# ESP32_Watch_Project_V2_0.net
KiCad netlist of a schematic drawn in Altium Designer
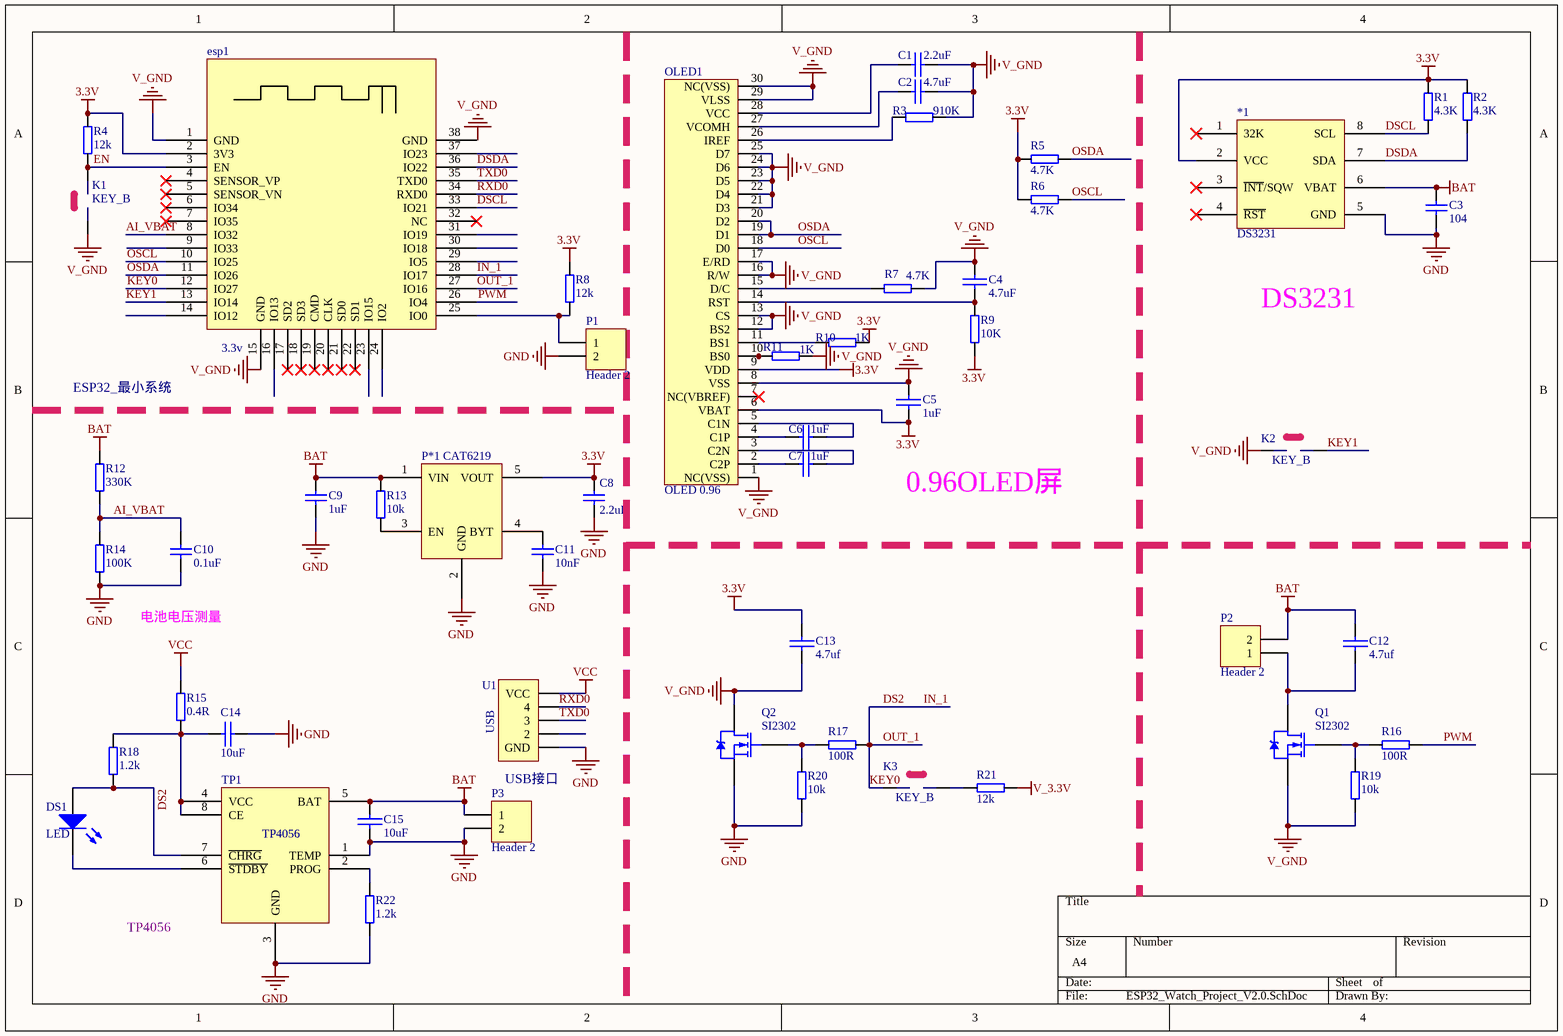
[diagram p0: ESP32_Watch_Project_V2.0.SchDoc]

(export (version "E")
  (design (tool "Eeschema 10.0.6"))
  (components
    (comp (ref "*1")
      (value "DS3231")
      (footprint "2104")
      (libsource (lib "ESP32_DOWN_Project") (part "DS3231"))
    )
    (comp (ref "C1")
      (value "2.2uF")
      (footprint "ESP32_DOWN_1_6:R0603")
      (description "Capacitor")
      (libsource (lib "ZigBee应用模块V2.1") (part "CAP"))
    )
    (comp (ref "C2")
      (value "4.7uF")
      (footprint "R0603")
      (description "Capacitor")
      (libsource (lib "ZigBee应用模块V2.1") (part "CAP"))
    )
    (comp (ref "C3")
      (value "104")
      (footprint "R0603")
      (description "Capacitor")
      (fields (field (name "PUBLISHER") "Altium Limited"))
      (libsource (lib "蓝牙可穿戴") (part "Cap_1"))
    )
    (comp (ref "C4")
      (value "4.7uF")
      (footprint "R0603")
      (description "Capacitor")
      (libsource (lib "ZigBee应用模块V2.1") (part "CAP"))
    )
    (comp (ref "C5")
      (value "1uF")
      (footprint "R0603")
      (description "Capacitor")
      (libsource (lib "ZigBee应用模块V2.1") (part "CAP"))
    )
    (comp (ref "C6")
      (value "1uF")
      (footprint "ESP32_DOWN_1_6:R0603")
      (description "Capacitor")
      (libsource (lib "ZigBee应用模块V2.1") (part "CAP"))
    )
    (comp (ref "C7")
      (value "1uF")
      (footprint "ESP32_DOWN_1_6:R0603")
      (description "Capacitor")
      (libsource (lib "ZigBee应用模块V2.1") (part "CAP"))
    )
    (comp (ref "C8")
      (value "2.2uF")
      (footprint "R0603")
      (description "Capacitor")
      (fields (field (name "PUBLISHER") "Altium Limited"))
      (libsource (lib "CC26XX转接板") (part "Cap_1"))
    )
    (comp (ref "C9")
      (value "1uF")
      (footprint "R0603")
      (description "Capacitor")
      (fields (field (name "PUBLISHER") "Altium Limited"))
      (libsource (lib "CC26XX转接板") (part "Cap_1"))
    )
    (comp (ref "C10")
      (value "0.1uF")
      (footprint "R0603")
      (description "Capacitor")
      (fields (field (name "PUBLISHER") "Altium Limited"))
      (libsource (lib "CC26XX转接板") (part "Cap_1"))
    )
    (comp (ref "C11")
      (value "10nF")
      (footprint "R0603")
      (description "Capacitor")
      (fields (field (name "PUBLISHER") "Altium Limited"))
      (libsource (lib "CC26XX转接板") (part "Cap_1"))
    )
    (comp (ref "C12")
      (value "4.7uf")
      (footprint "ESP32_DOWN_1_6:R0603")
      (description "Capacitor")
      (libsource (lib "ZigBee应用模块V2.1") (part "CAP"))
    )
    (comp (ref "C13")
      (value "4.7uf")
      (footprint "ESP32_DOWN_1_6:R0603")
      (description "Capacitor")
      (libsource (lib "ZigBee应用模块V2.1") (part "CAP"))
    )
    (comp (ref "C14")
      (value "10uF")
      (footprint "R0603")
      (description "Capacitor")
      (libsource (lib "ZigBee应用模块V2.1") (part "CAP"))
    )
    (comp (ref "C15")
      (value "10uF")
      (footprint "R0603")
      (description "Capacitor")
      (libsource (lib "ZigBee应用模块V2.1") (part "CAP"))
    )
    (comp (ref "DS1")
      (value "LED")
      (footprint "SMDLED")
      (description "Typical RED, GREEN, YELLOW, AMBER GaAs LED")
      (fields (field (name "PUBLISHER") "Altium Limited"))
      (libsource (lib "战舰STM32开发板底板封装库") (part "LED2"))
    )
    (comp (ref "esp1")
      (value "3.3v")
      (footprint "esp32_cord")
      (libsource (lib "ESP32_DOWN_Project") (part "esp32_core"))
    )
    (comp (ref "K1") (value "KEY_B") (footprint "KEY_b") (libsource (lib "ESP32_UP_Project") (part "KEY_B")))
    (comp (ref "K2")
      (value "KEY_B")
      (footprint "ESP32_DOWN_1_6:KEY_b")
      (libsource (lib "蓝牙可穿戴") (part "KEY_B"))
    )
    (comp (ref "K3")
      (value "KEY_B")
      (footprint "ESP32_DOWN_1_6:KEY_b")
      (libsource (lib "蓝牙可穿戴") (part "KEY_B"))
    )
    (comp (ref "OLED1") (value "OLED 0.96") (footprint "0.96_OLED") (libsource (lib "蓝牙可穿戴") (part "OLED")))
    (comp (ref "P*1")
      (value "CAT6219")
      (footprint "CAT6219")
      (libsource (lib "ESP32_DOWN_Project") (part "CAT6219"))
    )
    (comp (ref "P1")
      (value "Header 2")
      (footprint "HDR1X2")
      (description "Header, 2-Pin")
      (fields (field (name "PUBLISHER") "Altium Limited"))
      (libsource (lib "") (part "Header 2_1"))
    )
    (comp (ref "P2")
      (value "Header 2")
      (footprint "HDR1X2")
      (description "Header, 2-Pin")
      (fields (field (name "PUBLISHER") "Altium Limited"))
      (libsource (lib "Miscellaneous Connectors") (part "Header 2"))
    )
    (comp (ref "P3")
      (value "Header 2")
      (footprint "HDR1X2")
      (description "Header, 2-Pin")
      (fields (field (name "PUBLISHER") "Altium Limited"))
      (libsource (lib "") (part "Header 2_1"))
    )
    (comp (ref "Q1")
      (value "SI2302")
      (footprint "SOT-23(SOT-23-3)")
      (description "N-Channel Power MOSFET")
      (fields (field (name "PUBLISHER") "mazhongwei"))
      (libsource (lib "RoboFly") (part "SI2302"))
    )
    (comp (ref "Q2")
      (value "SI2302")
      (footprint "SOT-23(SOT-23-3)")
      (description "N-Channel Power MOSFET")
      (fields (field (name "PUBLISHER") "mazhongwei"))
      (libsource (lib "RoboFly") (part "SI2302"))
    )
    (comp (ref "R1") (value "4.3K") (footprint "C0603") (libsource (lib "蓝牙可穿戴") (part "Res")))
    (comp (ref "R2") (value "4.3K") (footprint "C0603") (libsource (lib "蓝牙可穿戴") (part "Res")))
    (comp (ref "R3") (value "910K") (footprint "C0603") (libsource (lib "蓝牙可穿戴") (part "Res")))
    (comp (ref "R4") (value "12k") (footprint "C0603") (libsource (lib "蓝牙可穿戴") (part "Res")))
    (comp (ref "R5") (value "4.7K") (footprint "C0603") (libsource (lib "蓝牙可穿戴") (part "Res")))
    (comp (ref "R6") (value "4.7K") (footprint "C0603") (libsource (lib "蓝牙可穿戴") (part "Res")))
    (comp (ref "R7") (value "4.7K") (footprint "C0603") (libsource (lib "蓝牙可穿戴") (part "Res")))
    (comp (ref "R8") (value "12k") (footprint "C0603") (libsource (lib "蓝牙可穿戴") (part "Res")))
    (comp (ref "R9") (value "10K") (footprint "C0603") (libsource (lib "蓝牙可穿戴") (part "Res")))
    (comp (ref "R10") (value "1K") (footprint "C0603") (libsource (lib "蓝牙可穿戴") (part "Res")))
    (comp (ref "R11") (value "1K") (footprint "C0603") (libsource (lib "蓝牙可穿戴") (part "Res")))
    (comp (ref "R12") (value "330K") (footprint "C0603") (libsource (lib "蓝牙可穿戴") (part "Res")))
    (comp (ref "R13") (value "10k") (footprint "C0603") (libsource (lib "蓝牙可穿戴") (part "Res")))
    (comp (ref "R14") (value "100K") (footprint "C0603") (libsource (lib "蓝牙可穿戴") (part "Res")))
    (comp (ref "R15") (value "0.4R") (footprint "C0603") (libsource (lib "蓝牙可穿戴") (part "Res")))
    (comp (ref "R16") (value "100R") (footprint "C0603") (libsource (lib "蓝牙可穿戴") (part "Res")))
    (comp (ref "R17") (value "100R") (footprint "C0603") (libsource (lib "蓝牙可穿戴") (part "Res")))
    (comp (ref "R18") (value "1.2k") (footprint "C0603") (libsource (lib "蓝牙可穿戴") (part "Res")))
    (comp (ref "R19") (value "10k") (footprint "C0603") (libsource (lib "蓝牙可穿戴") (part "Res")))
    (comp (ref "R20") (value "10k") (footprint "C0603") (libsource (lib "蓝牙可穿戴") (part "Res")))
    (comp (ref "R21") (value "12k") (footprint "C0603") (libsource (lib "蓝牙可穿戴") (part "Res")))
    (comp (ref "R22") (value "1.2k") (footprint "C0603") (libsource (lib "蓝牙可穿戴") (part "Res")))
    (comp (ref "TP1") (value "TP4056") (footprint "2104") (libsource (lib "TP4056") (part "TP4056")))
    (comp (ref "U1") (value "U?") (footprint "type_a") (libsource (lib "ESP32_DOWN_Project") (part "type_a")))
  )
  (nets
    (net (code "1") (name "/AI_VBAT") (class "Default")
      (node (ref "C10") (pin "2") (pinfunction "2_2") (pintype "passive"))
      (node (ref "R12") (pin "1") (pintype "passive"))
      (node (ref "R14") (pin "2") (pintype "passive"))
      (node (ref "esp1") (pin "8") (pinfunction "IO32_8") (pintype "passive"))
    )
    (net (code "2") (name "/DS2") (class "Default")
      (node (ref "DS1") (pin "1") (pinfunction "A_1") (pintype "passive"))
      (node (ref "R17") (pin "1") (pintype "passive"))
      (node (ref "R18") (pin "2") (pintype "passive"))
      (node (ref "TP1") (pin "7") (pinfunction "~{CHRG}_7") (pintype "passive"))
      (node (ref "esp1") (pin "27") (pinfunction "IO16_27") (pintype "passive"))
      (node (ref "esp1") (pin "28") (pinfunction "IO17_28") (pintype "passive"))
    )
    (net (code "3") (name "/DSCL") (class "Default")
      (node (ref "*1") (pin "8") (pinfunction "SCL_8") (pintype "passive"))
      (node (ref "R1") (pin "2") (pintype "passive"))
      (node (ref "esp1") (pin "33") (pinfunction "IO21_33") (pintype "passive"))
    )
    (net (code "4") (name "/DSDA") (class "Default")
      (node (ref "*1") (pin "7") (pinfunction "SDA_7") (pintype "passive"))
      (node (ref "R2") (pin "2") (pintype "passive"))
      (node (ref "esp1") (pin "36") (pinfunction "IO22_36") (pintype "passive"))
    )
    (net (code "5") (name "/EN") (class "Default")
      (node (ref "K1") (pin "2") (pinfunction "2_2") (pintype "passive"))
      (node (ref "R4") (pin "1") (pintype "passive"))
      (node (ref "esp1") (pin "3") (pinfunction "EN_3") (pintype "passive"))
    )
    (net (code "6") (name "/KEY0") (class "Default")
      (node (ref "K3") (pin "1") (pinfunction "1_1") (pintype "passive"))
      (node (ref "esp1") (pin "12") (pinfunction "IO27_12") (pintype "passive"))
    )
    (net (code "7") (name "/KEY1") (class "Default")
      (node (ref "K2") (pin "2") (pinfunction "2_2") (pintype "passive"))
      (node (ref "esp1") (pin "13") (pinfunction "IO14_13") (pintype "passive"))
    )
    (net (code "8") (name "/OSCL") (class "Default")
      (node (ref "OLED1") (pin "18") (pinfunction "D0_18") (pintype "passive"))
      (node (ref "R6") (pin "1") (pintype "passive"))
      (node (ref "esp1") (pin "10") (pinfunction "IO25_10") (pintype "passive"))
    )
    (net (code "9") (name "/OSDA") (class "Default")
      (node (ref "OLED1") (pin "19") (pinfunction "D1_19") (pintype "passive"))
      (node (ref "OLED1") (pin "20") (pinfunction "D2_20") (pintype "passive"))
      (node (ref "R5") (pin "1") (pintype "passive"))
      (node (ref "esp1") (pin "11") (pinfunction "IO26_11") (pintype "passive"))
    )
    (net (code "10") (name "/PWM") (class "Default")
      (node (ref "R16") (pin "1") (pintype "passive"))
      (node (ref "esp1") (pin "26") (pinfunction "IO4_26") (pintype "passive"))
    )
    (net (code "11") (name "/RXD0") (class "Default")
      (node (ref "U1") (pin "4") (pinfunction "4_4") (pintype "passive"))
      (node (ref "esp1") (pin "34") (pinfunction "RXD0_34") (pintype "passive"))
    )
    (net (code "12") (name "/TXD0") (class "Default")
      (node (ref "U1") (pin "3") (pinfunction "3_3") (pintype "passive"))
      (node (ref "esp1") (pin "35") (pinfunction "TXD0_35") (pintype "passive"))
    )
    (net (code "13") (name "3.3V") (class "Default")
      (node (ref "*1") (pin "2") (pinfunction "VCC_2") (pintype "passive"))
      (node (ref "C13") (pin "1") (pinfunction "1_1") (pintype "passive"))
      (node (ref "C5") (pin "1") (pinfunction "1_1") (pintype "passive"))
      (node (ref "C8") (pin "2") (pinfunction "2_2") (pintype "passive"))
      (node (ref "OLED1") (pin "6") (pinfunction "VBAT_6") (pintype "passive"))
      (node (ref "OLED1") (pin "9") (pinfunction "VDD_9") (pintype "passive"))
      (node (ref "P*1") (pin "5") (pinfunction "VOUT_5") (pintype "passive"))
      (node (ref "R1") (pin "1") (pintype "passive"))
      (node (ref "R10") (pin "1") (pintype "passive"))
      (node (ref "R2") (pin "1") (pintype "passive"))
      (node (ref "R4") (pin "2") (pintype "passive"))
      (node (ref "R5") (pin "2") (pintype "passive"))
      (node (ref "R6") (pin "2") (pintype "passive"))
      (node (ref "R8") (pin "2") (pintype "passive"))
      (node (ref "R9") (pin "2") (pintype "passive"))
      (node (ref "esp1") (pin "2") (pinfunction "3V3_2") (pintype "passive"))
    )
    (net (code "14") (name "BAT") (class "Default")
      (node (ref "*1") (pin "6") (pinfunction "VBAT_6") (pintype "passive"))
      (node (ref "C12") (pin "1") (pinfunction "1_1") (pintype "passive"))
      (node (ref "C15") (pin "2") (pinfunction "2_2") (pintype "passive"))
      (node (ref "C3") (pin "2") (pinfunction "2_2") (pintype "passive"))
      (node (ref "C9") (pin "2") (pinfunction "2_2") (pintype "passive"))
      (node (ref "P*1") (pin "1") (pinfunction "VIN_1") (pintype "passive"))
      (node (ref "P2") (pin "2") (pinfunction "2_2") (pintype "passive"))
      (node (ref "P3") (pin "1") (pinfunction "1_1") (pintype "passive"))
      (node (ref "R12") (pin "2") (pintype "passive"))
      (node (ref "R13") (pin "2") (pintype "passive"))
      (node (ref "TP1") (pin "5") (pinfunction "BAT_5") (pintype "passive"))
    )
    (net (code "15") (name "GND") (class "Default")
      (node (ref "*1") (pin "5") (pinfunction "GND_5") (pintype "passive"))
      (node (ref "C10") (pin "1") (pinfunction "1_1") (pintype "passive"))
      (node (ref "C11") (pin "1") (pinfunction "1_1") (pintype "passive"))
      (node (ref "C14") (pin "2") (pinfunction "2_2") (pintype "passive"))
      (node (ref "C15") (pin "1") (pinfunction "1_1") (pintype "passive"))
      (node (ref "C3") (pin "1") (pinfunction "1_1") (pintype "passive"))
      (node (ref "C8") (pin "1") (pinfunction "1_1") (pintype "passive"))
      (node (ref "C9") (pin "1") (pinfunction "1_1") (pintype "passive"))
      (node (ref "P*1") (pin "2") (pinfunction "GND_2") (pintype "passive"))
      (node (ref "P1") (pin "2") (pinfunction "2_2") (pintype "passive"))
      (node (ref "P3") (pin "2") (pinfunction "2_2") (pintype "passive"))
      (node (ref "Q2") (pin "2") (pinfunction "S_2") (pintype "passive"))
      (node (ref "R14") (pin "1") (pintype "passive"))
      (node (ref "R20") (pin "1") (pintype "passive"))
      (node (ref "R22") (pin "2") (pintype "passive"))
      (node (ref "TP1") (pin "1") (pinfunction "TEMP_1") (pintype "passive"))
      (node (ref "TP1") (pin "3") (pinfunction "GND_3") (pintype "passive"))
      (node (ref "U1") (pin "1") (pinfunction "GND_1") (pintype "passive"))
    )
    (net (code "16") (name "Net-(DS1-K)") (class "Default")
      (node (ref "DS1") (pin "2") (pinfunction "K_2") (pintype "passive"))
      (node (ref "TP1") (pin "6") (pinfunction "~{STDBY}_6") (pintype "passive"))
    )
    (net (code "17") (name "Net-(K3-Pad2)") (class "Default")
      (node (ref "K3") (pin "2") (pinfunction "2_2") (pintype "passive"))
      (node (ref "R21") (pin "2") (pintype "passive"))
    )
    (net (code "18") (name "Net-(OLED1-BS0)") (class "Default")
      (node (ref "OLED1") (pin "10") (pinfunction "BS0_10") (pintype "passive"))
      (node (ref "R11") (pin "2") (pintype "passive"))
    )
    (net (code "19") (name "Net-(OLED1-BS1)") (class "Default")
      (node (ref "OLED1") (pin "11") (pinfunction "BS1_11") (pintype "passive"))
      (node (ref "R10") (pin "2") (pintype "passive"))
    )
    (net (code "20") (name "Net-(OLED1-C1N)") (class "Default")
      (node (ref "C6") (pin "1") (pinfunction "1_1") (pintype "passive"))
      (node (ref "OLED1") (pin "5") (pinfunction "C1N_5") (pintype "passive"))
    )
    (net (code "21") (name "Net-(OLED1-C1P)") (class "Default")
      (node (ref "C6") (pin "2") (pinfunction "2_2") (pintype "passive"))
      (node (ref "OLED1") (pin "4") (pinfunction "C1P_4") (pintype "passive"))
    )
    (net (code "22") (name "Net-(OLED1-C2N)") (class "Default")
      (node (ref "C7") (pin "1") (pinfunction "1_1") (pintype "passive"))
      (node (ref "OLED1") (pin "3") (pinfunction "C2N_3") (pintype "passive"))
    )
    (net (code "23") (name "Net-(OLED1-C2P)") (class "Default")
      (node (ref "C7") (pin "2") (pinfunction "2_2") (pintype "passive"))
      (node (ref "OLED1") (pin "2") (pinfunction "C2P_2") (pintype "passive"))
    )
    (net (code "24") (name "Net-(OLED1-D3)") (class "Default")
      (node (ref "OLED1") (pin "21") (pinfunction "D3_21") (pintype "passive"))
      (node (ref "OLED1") (pin "22") (pinfunction "D4_22") (pintype "passive"))
      (node (ref "OLED1") (pin "23") (pinfunction "D5_23") (pintype "passive"))
      (node (ref "OLED1") (pin "24") (pinfunction "D6_24") (pintype "passive"))
      (node (ref "OLED1") (pin "25") (pinfunction "D7_25") (pintype "passive"))
    )
    (net (code "25") (name "Net-(OLED1-D{slash}C)") (class "Default")
      (node (ref "OLED1") (pin "15") (pinfunction "D/C_15") (pintype "passive"))
      (node (ref "R7") (pin "1") (pintype "passive"))
    )
    (net (code "26") (name "Net-(OLED1-IREF)") (class "Default")
      (node (ref "OLED1") (pin "26") (pinfunction "IREF_26") (pintype "passive"))
      (node (ref "R3") (pin "1") (pintype "passive"))
    )
    (net (code "27") (name "Net-(OLED1-RST)") (class "Default")
      (node (ref "C4") (pin "1") (pinfunction "1_1") (pintype "passive"))
      (node (ref "OLED1") (pin "14") (pinfunction "RST_14") (pintype "passive"))
      (node (ref "R9") (pin "1") (pintype "passive"))
    )
    (net (code "28") (name "Net-(OLED1-VCC)") (class "Default")
      (node (ref "C1") (pin "1") (pinfunction "1_1") (pintype "passive"))
      (node (ref "OLED1") (pin "28") (pinfunction "VCC_28") (pintype "passive"))
    )
    (net (code "29") (name "Net-(OLED1-VCOMH)") (class "Default")
      (node (ref "C2") (pin "1") (pinfunction "1_1") (pintype "passive"))
      (node (ref "OLED1") (pin "27") (pinfunction "VCOMH_27") (pintype "passive"))
    )
    (net (code "30") (name "Net-(P*1-BYT)") (class "Default")
      (node (ref "C11") (pin "2") (pinfunction "2_2") (pintype "passive"))
      (node (ref "P*1") (pin "4") (pinfunction "BYT_4") (pintype "passive"))
    )
    (net (code "31") (name "Net-(P*1-EN)") (class "Default")
      (node (ref "P*1") (pin "3") (pinfunction "EN_3") (pintype "passive"))
      (node (ref "R13") (pin "1") (pintype "passive"))
    )
    (net (code "32") (name "Net-(Q1-D)") (class "Default")
      (node (ref "C12") (pin "2") (pinfunction "2_2") (pintype "passive"))
      (node (ref "P2") (pin "1") (pinfunction "1_1") (pintype "passive"))
      (node (ref "Q1") (pin "3") (pinfunction "D_3") (pintype "passive"))
    )
    (net (code "33") (name "Net-(Q1-G)") (class "Default")
      (node (ref "Q1") (pin "1") (pinfunction "G_1") (pintype "passive"))
      (node (ref "R16") (pin "2") (pintype "passive"))
      (node (ref "R19") (pin "2") (pintype "passive"))
    )
    (net (code "34") (name "Net-(Q2-G)") (class "Default")
      (node (ref "Q2") (pin "1") (pinfunction "G_1") (pintype "passive"))
      (node (ref "R17") (pin "2") (pintype "passive"))
      (node (ref "R20") (pin "2") (pintype "passive"))
    )
    (net (code "35") (name "Net-(TP1-CE)") (class "Default")
      (node (ref "C14") (pin "1") (pinfunction "1_1") (pintype "passive"))
      (node (ref "R15") (pin "2") (pintype "passive"))
      (node (ref "R18") (pin "1") (pintype "passive"))
      (node (ref "TP1") (pin "4") (pinfunction "VCC_4") (pintype "passive"))
      (node (ref "TP1") (pin "8") (pinfunction "CE_8") (pintype "passive"))
    )
    (net (code "36") (name "Net-(TP1-PROG)") (class "Default")
      (node (ref "R22") (pin "1") (pintype "passive"))
      (node (ref "TP1") (pin "2") (pinfunction "PROG_2") (pintype "passive"))
    )
    (net (code "37") (name "Net-(esp1-IO0)") (class "Default")
      (node (ref "P1") (pin "1") (pinfunction "1_1") (pintype "passive"))
      (node (ref "R8") (pin "1") (pintype "passive"))
      (node (ref "esp1") (pin "25") (pinfunction "IO0_25") (pintype "passive"))
    )
    (net (code "38") (name "VCC") (class "Default")
      (node (ref "R15") (pin "1") (pintype "passive"))
      (node (ref "U1") (pin "5") (pinfunction "VCC_5") (pintype "passive"))
    )
    (net (code "39") (name "V_3.3V") (class "Default") (node (ref "R21") (pin "1") (pintype "passive")))
    (net (code "40") (name "V_GND") (class "Default")
      (node (ref "C1") (pin "2") (pinfunction "2_2") (pintype "passive"))
      (node (ref "C13") (pin "2") (pinfunction "2_2") (pintype "passive"))
      (node (ref "C2") (pin "2") (pinfunction "2_2") (pintype "passive"))
      (node (ref "C4") (pin "2") (pinfunction "2_2") (pintype "passive"))
      (node (ref "C5") (pin "2") (pinfunction "2_2") (pintype "passive"))
      (node (ref "K1") (pin "1") (pinfunction "1_1") (pintype "passive"))
      (node (ref "OLED1") (pin "1") (pinfunction "NC(VSS)_1") (pintype "passive"))
      (node (ref "OLED1") (pin "12") (pinfunction "BS2_12") (pintype "passive"))
      (node (ref "OLED1") (pin "13") (pinfunction "CS_13") (pintype "passive"))
      (node (ref "OLED1") (pin "16") (pinfunction "R/W_16") (pintype "passive"))
      (node (ref "OLED1") (pin "17") (pinfunction "E/RD_17") (pintype "passive"))
      (node (ref "OLED1") (pin "29") (pinfunction "VLSS_29") (pintype "passive"))
      (node (ref "OLED1") (pin "30") (pinfunction "NC(VSS)_30") (pintype "passive"))
      (node (ref "OLED1") (pin "8") (pinfunction "VSS_8") (pintype "passive"))
      (node (ref "Q1") (pin "2") (pinfunction "S_2") (pintype "passive"))
      (node (ref "Q2") (pin "3") (pinfunction "D_3") (pintype "passive"))
      (node (ref "R11") (pin "1") (pintype "passive"))
      (node (ref "R19") (pin "1") (pintype "passive"))
      (node (ref "R3") (pin "2") (pintype "passive"))
      (node (ref "R7") (pin "2") (pintype "passive"))
      (node (ref "esp1") (pin "1") (pinfunction "GND_1") (pintype "passive"))
      (node (ref "esp1") (pin "15") (pinfunction "GND_15") (pintype "passive"))
    )
    (net (code "41") (name "unconnected-(*1-32K-Pad1)") (class "Default")
      (node (ref "*1") (pin "1") (pinfunction "32K_1") (pintype "passive+no_connect"))
    )
    (net (code "42") (name "unconnected-(*1-~{INT}{slash}SQW-Pad3)") (class "Default")
      (node (ref "*1") (pin "3") (pinfunction "~{INT}/SQW_3") (pintype "passive+no_connect"))
    )
    (net (code "43") (name "unconnected-(*1-~{RST}-Pad4)") (class "Default")
      (node (ref "*1") (pin "4") (pinfunction "~{RST}_4") (pintype "passive+no_connect"))
    )
    (net (code "44") (name "unconnected-(K2-Pad1)") (class "Default")
      (node (ref "K2") (pin "1") (pinfunction "1_1") (pintype "passive"))
    )
    (net (code "45") (name "unconnected-(OLED1-NC(VBREF)-Pad7)") (class "Default")
      (node (ref "OLED1") (pin "7") (pinfunction "NC(VBREF)_7") (pintype "passive+no_connect"))
    )
    (net (code "46") (name "unconnected-(U1-Pad2)") (class "Default")
      (node (ref "U1") (pin "2") (pinfunction "2_2") (pintype "passive"))
    )
    (net (code "47") (name "unconnected-(esp1-CLK-Pad20)") (class "Default")
      (node (ref "esp1") (pin "20") (pinfunction "CLK_20") (pintype "passive+no_connect"))
    )
    (net (code "48") (name "unconnected-(esp1-CMD-Pad19)") (class "Default")
      (node (ref "esp1") (pin "19") (pinfunction "CMD_19") (pintype "passive+no_connect"))
    )
    (net (code "49") (name "unconnected-(esp1-GND-Pad38)") (class "Default")
      (node (ref "esp1") (pin "38") (pinfunction "GND_38") (pintype "passive"))
    )
    (net (code "50") (name "unconnected-(esp1-IO2-Pad24)") (class "Default")
      (node (ref "esp1") (pin "24") (pinfunction "IO2_24") (pintype "passive"))
    )
    (net (code "51") (name "unconnected-(esp1-IO5-Pad29)") (class "Default")
      (node (ref "esp1") (pin "29") (pinfunction "IO5_29") (pintype "passive"))
    )
    (net (code "52") (name "unconnected-(esp1-IO12-Pad14)") (class "Default")
      (node (ref "esp1") (pin "14") (pinfunction "IO12_14") (pintype "passive"))
    )
    (net (code "53") (name "unconnected-(esp1-IO13-Pad16)") (class "Default")
      (node (ref "esp1") (pin "16") (pinfunction "IO13_16") (pintype "passive"))
    )
    (net (code "54") (name "unconnected-(esp1-IO15-Pad23)") (class "Default")
      (node (ref "esp1") (pin "23") (pinfunction "IO15_23") (pintype "passive"))
    )
    (net (code "55") (name "unconnected-(esp1-IO18-Pad30)") (class "Default")
      (node (ref "esp1") (pin "30") (pinfunction "IO18_30") (pintype "passive"))
    )
    (net (code "56") (name "unconnected-(esp1-IO19-Pad31)") (class "Default")
      (node (ref "esp1") (pin "31") (pinfunction "IO19_31") (pintype "passive"))
    )
    (net (code "57") (name "unconnected-(esp1-IO23-Pad37)") (class "Default")
      (node (ref "esp1") (pin "37") (pinfunction "IO23_37") (pintype "passive"))
    )
    (net (code "58") (name "unconnected-(esp1-IO33-Pad9)") (class "Default")
      (node (ref "esp1") (pin "9") (pinfunction "IO33_9") (pintype "passive"))
    )
    (net (code "59") (name "unconnected-(esp1-IO34-Pad6)") (class "Default")
      (node (ref "esp1") (pin "6") (pinfunction "IO34_6") (pintype "passive+no_connect"))
    )
    (net (code "60") (name "unconnected-(esp1-IO35-Pad7)") (class "Default")
      (node (ref "esp1") (pin "7") (pinfunction "IO35_7") (pintype "passive+no_connect"))
    )
    (net (code "61") (name "unconnected-(esp1-NC-Pad32)") (class "Default")
      (node (ref "esp1") (pin "32") (pinfunction "NC_32") (pintype "passive+no_connect"))
    )
    (net (code "62") (name "unconnected-(esp1-SD0-Pad21)") (class "Default")
      (node (ref "esp1") (pin "21") (pinfunction "SD0_21") (pintype "passive+no_connect"))
    )
    (net (code "63") (name "unconnected-(esp1-SD1-Pad22)") (class "Default")
      (node (ref "esp1") (pin "22") (pinfunction "SD1_22") (pintype "passive+no_connect"))
    )
    (net (code "64") (name "unconnected-(esp1-SD2-Pad17)") (class "Default")
      (node (ref "esp1") (pin "17") (pinfunction "SD2_17") (pintype "passive+no_connect"))
    )
    (net (code "65") (name "unconnected-(esp1-SD3-Pad18)") (class "Default")
      (node (ref "esp1") (pin "18") (pinfunction "SD3_18") (pintype "passive+no_connect"))
    )
    (net (code "66") (name "unconnected-(esp1-SENSOR_VN-Pad5)") (class "Default")
      (node (ref "esp1") (pin "5") (pinfunction "SENSOR_VN_5") (pintype "passive+no_connect"))
    )
    (net (code "67") (name "unconnected-(esp1-SENSOR_VP-Pad4)") (class "Default")
      (node (ref "esp1") (pin "4") (pinfunction "SENSOR_VP_4") (pintype "passive+no_connect"))
    )
  )
)
